# Auxiliary.net
KiCad netlist of a schematic drawn in Altium Designer
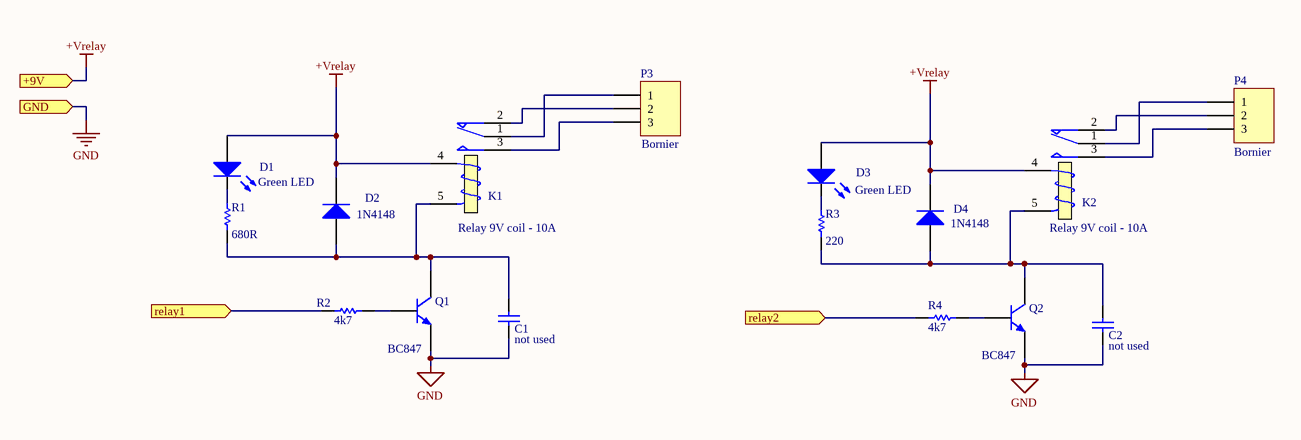
[diagram p0: Auxiliary.SchDoc]

(export (version "E")
  (design (tool "Eeschema 10.0.6"))
  (components
    (comp (ref "C1")
      (value "not used")
      (footprint "0805_W")
      (description "Capacitor")
      (libsource (lib "Miscellaneous Devices") (part "Cap"))
    )
    (comp (ref "C2")
      (value "not used")
      (footprint "0805_W")
      (description "Capacitor")
      (libsource (lib "Miscellaneous Devices") (part "Cap"))
    )
    (comp (ref "D1")
      (value "Green LED")
      (footprint "LED_0805")
      (description "Typical INFRARED GaAs LED")
      (libsource (lib "Miscellaneous Devices") (part "LED0"))
    )
    (comp (ref "D2")
      (value "1N4148")
      (footprint "SOD-123")
      (description "High Conductance Fast Diode")
      (libsource (lib "Miscellaneous Devices") (part "Diode 1N4148"))
    )
    (comp (ref "D3")
      (value "Green LED")
      (footprint "LED_0805")
      (description "Typical INFRARED GaAs LED")
      (libsource (lib "Miscellaneous Devices") (part "LED0"))
    )
    (comp (ref "D4")
      (value "1N4148")
      (footprint "SOD-123")
      (description "High Conductance Fast Diode")
      (libsource (lib "Miscellaneous Devices") (part "Diode 1N4148"))
    )
    (comp (ref "K1")
      (value "Relay 9V coil - 10A")
      (footprint "Relay - SPDT")
      (description "SPDT Relay")
      (libsource (lib "Miscellaneous Devices") (part "Relay"))
    )
    (comp (ref "K2")
      (value "Relay 9V coil - 10A")
      (footprint "Relay - SPDT")
      (description "SPDT Relay")
      (libsource (lib "Miscellaneous Devices") (part "Relay"))
    )
    (comp (ref "P3")
      (value "Bornier")
      (footprint "KK-3_G")
      (description "Header, 3-Pin")
      (libsource (lib "AQAC") (part "Header 3"))
    )
    (comp (ref "P4")
      (value "Bornier")
      (footprint "KK-3_G")
      (description "Header, 3-Pin")
      (libsource (lib "AQAC") (part "Header 3"))
    )
    (comp (ref "Q1")
      (value "BC847")
      (footprint "SOT-23-TT3_L")
      (description "NPN General-purpose Transistor")
      (libsource (lib "Philips Discrete BJT - Low Power") (part "BC847"))
    )
    (comp (ref "Q2")
      (value "BC847")
      (footprint "SOT-23-TT3_L")
      (description "NPN General-purpose Transistor")
      (libsource (lib "Philips Discrete BJT - Low Power") (part "BC847"))
    )
    (comp (ref "R1")
      (value "680R")
      (footprint "0805_W")
      (description "Resistor")
      (libsource (lib "Inversor_LCEE") (part "Res_0805"))
    )
    (comp (ref "R2")
      (value "4k7")
      (footprint "0805_W")
      (description "Resistor")
      (libsource (lib "Miscellaneous Devices") (part "Res1"))
    )
    (comp (ref "R3")
      (value "220")
      (footprint "0805_W")
      (description "Resistor")
      (libsource (lib "Inversor_LCEE") (part "Res_0805"))
    )
    (comp (ref "R4")
      (value "4k7")
      (footprint "0805_W")
      (description "Resistor")
      (libsource (lib "Miscellaneous Devices") (part "Res1"))
    )
  )
  (nets
    (net (code "1") (name "+Vrelay") (class "Default")
      (node (ref "D1") (pin "1") (pinfunction "A_1") (pintype "passive"))
      (node (ref "D2") (pin "2") (pinfunction "K_2") (pintype "passive"))
      (node (ref "D3") (pin "1") (pinfunction "A_1") (pintype "passive"))
      (node (ref "D4") (pin "2") (pinfunction "K_2") (pintype "passive"))
      (node (ref "K1") (pin "4") (pinfunction "T1_4") (pintype "passive"))
      (node (ref "K2") (pin "4") (pinfunction "T1_4") (pintype "passive"))
    )
    (net (code "2") (name "/relay1") (class "Default")
      (node (ref "R2") (pin "1") (pinfunction "1_1") (pintype "passive"))
    )
    (net (code "3") (name "/relay2") (class "Default")
      (node (ref "R4") (pin "1") (pinfunction "1_1") (pintype "passive"))
    )
    (net (code "4") (name "GND") (class "Default")
      (node (ref "C1") (pin "1") (pinfunction "1_1") (pintype "passive"))
      (node (ref "C2") (pin "1") (pinfunction "1_1") (pintype "passive"))
      (node (ref "Q1") (pin "2") (pinfunction "E_2") (pintype "passive"))
      (node (ref "Q2") (pin "2") (pinfunction "E_2") (pintype "passive"))
    )
    (net (code "5") (name "Net-(D1-K)") (class "Default")
      (node (ref "D1") (pin "2") (pinfunction "K_2") (pintype "passive"))
      (node (ref "R1") (pin "1") (pinfunction "1_1") (pintype "passive"))
    )
    (net (code "6") (name "Net-(D2-A)") (class "Default")
      (node (ref "C1") (pin "2") (pinfunction "2_2") (pintype "passive"))
      (node (ref "D2") (pin "1") (pinfunction "A_1") (pintype "passive"))
      (node (ref "K1") (pin "5") (pinfunction "T2_5") (pintype "passive"))
      (node (ref "Q1") (pin "3") (pinfunction "C_3") (pintype "passive"))
      (node (ref "R1") (pin "2") (pinfunction "2_2") (pintype "passive"))
    )
    (net (code "7") (name "Net-(D3-K)") (class "Default")
      (node (ref "D3") (pin "2") (pinfunction "K_2") (pintype "passive"))
      (node (ref "R3") (pin "1") (pinfunction "1_1") (pintype "passive"))
    )
    (net (code "8") (name "Net-(D4-A)") (class "Default")
      (node (ref "C2") (pin "2") (pinfunction "2_2") (pintype "passive"))
      (node (ref "D4") (pin "1") (pinfunction "A_1") (pintype "passive"))
      (node (ref "K2") (pin "5") (pinfunction "T2_5") (pintype "passive"))
      (node (ref "Q2") (pin "3") (pinfunction "C_3") (pintype "passive"))
      (node (ref "R3") (pin "2") (pinfunction "2_2") (pintype "passive"))
    )
    (net (code "9") (name "Net-(K1-COM)") (class "Default")
      (node (ref "K1") (pin "1") (pinfunction "COM_1") (pintype "passive"))
      (node (ref "P3") (pin "1") (pinfunction "1_1") (pintype "passive"))
    )
    (net (code "10") (name "Net-(K1-NC)") (class "Default")
      (node (ref "K1") (pin "2") (pinfunction "NC_2") (pintype "passive"))
      (node (ref "P3") (pin "2") (pinfunction "2_2") (pintype "passive"))
    )
    (net (code "11") (name "Net-(K1-NO)") (class "Default")
      (node (ref "K1") (pin "3") (pinfunction "NO_3") (pintype "passive"))
      (node (ref "P3") (pin "3") (pinfunction "3_3") (pintype "passive"))
    )
    (net (code "12") (name "Net-(K2-COM)") (class "Default")
      (node (ref "K2") (pin "1") (pinfunction "COM_1") (pintype "passive"))
      (node (ref "P4") (pin "1") (pinfunction "1_1") (pintype "passive"))
    )
    (net (code "13") (name "Net-(K2-NC)") (class "Default")
      (node (ref "K2") (pin "2") (pinfunction "NC_2") (pintype "passive"))
      (node (ref "P4") (pin "2") (pinfunction "2_2") (pintype "passive"))
    )
    (net (code "14") (name "Net-(K2-NO)") (class "Default")
      (node (ref "K2") (pin "3") (pinfunction "NO_3") (pintype "passive"))
      (node (ref "P4") (pin "3") (pinfunction "3_3") (pintype "passive"))
    )
    (net (code "15") (name "Net-(Q1-B)") (class "Default")
      (node (ref "Q1") (pin "1") (pinfunction "B_1") (pintype "passive"))
      (node (ref "R2") (pin "2") (pinfunction "2_2") (pintype "passive"))
    )
    (net (code "16") (name "Net-(Q2-B)") (class "Default")
      (node (ref "Q2") (pin "1") (pinfunction "B_1") (pintype "passive"))
      (node (ref "R4") (pin "2") (pinfunction "2_2") (pintype "passive"))
    )
  )
)
